# mipi_to_lvds.net
KiCad netlist of a schematic drawn in Altium Designer
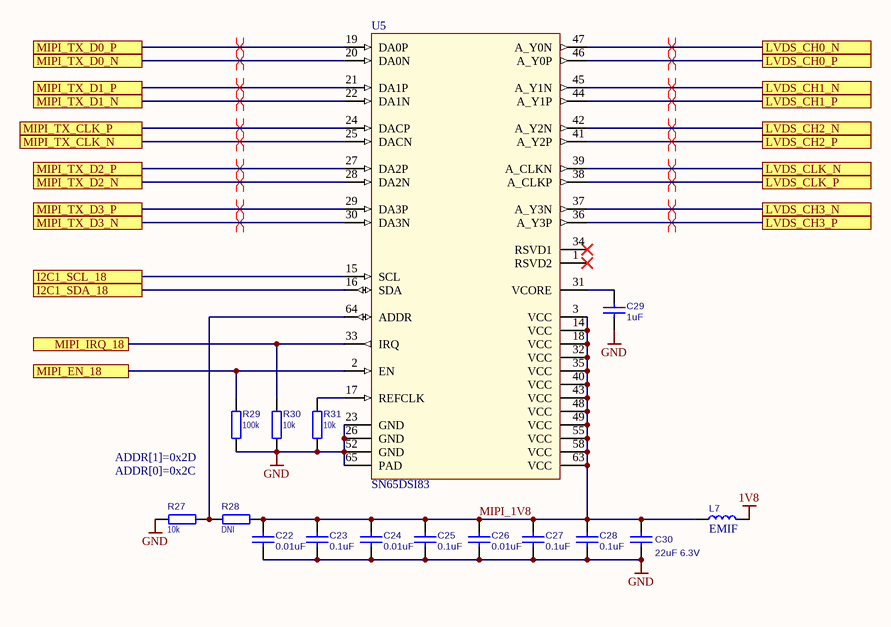
[diagram p0: mipi_to_lvds.SchDoc]

(export (version "E")
  (design (tool "Eeschema 10.0.6"))
  (components
    (comp (ref "C22")
      (value "0.01uF")
      (footprint "Capacitors:C0603")
      (description "CAP_NPOL")
      (fields (field (name "Comment") "CL10B103KB8NNNC"))
      (libsource (lib "capacitors") (part "CAP_NPOL"))
    )
    (comp (ref "C23")
      (value "0.1uF")
      (footprint "Capacitors:C0603")
      (description "CAP_NPOL")
      (fields (field (name "Comment") "C1608X7R1H104K080AA"))
      (libsource (lib "capacitors") (part "CAP_NPOL"))
    )
    (comp (ref "C24")
      (value "0.01uF")
      (footprint "Capacitors:C0603")
      (description "CAP_NPOL")
      (fields (field (name "Comment") "CL10B103KB8NNNC"))
      (libsource (lib "capacitors") (part "CAP_NPOL"))
    )
    (comp (ref "C25")
      (value "0.1uF")
      (footprint "Capacitors:C0603")
      (description "CAP_NPOL")
      (fields (field (name "Comment") "C1608X7R1H104K080AA"))
      (libsource (lib "capacitors") (part "CAP_NPOL"))
    )
    (comp (ref "C26")
      (value "0.01uF")
      (footprint "Capacitors:C0603")
      (description "CAP_NPOL")
      (fields (field (name "Comment") "CL10B103KB8NNNC"))
      (libsource (lib "capacitors") (part "CAP_NPOL"))
    )
    (comp (ref "C27")
      (value "0.1uF")
      (footprint "Capacitors:C0603")
      (description "CAP_NPOL")
      (fields (field (name "Comment") "C1608X7R1H104K080AA"))
      (libsource (lib "capacitors") (part "CAP_NPOL"))
    )
    (comp (ref "C28")
      (value "0.1uF")
      (footprint "Capacitors:C0603")
      (description "CAP_NPOL")
      (fields (field (name "Comment") "C1608X7R1H104K080AA"))
      (libsource (lib "capacitors") (part "CAP_NPOL"))
    )
    (comp (ref "C29")
      (value "1uF")
      (footprint "Capacitors:C0603")
      (description "CAP_NPOL")
      (fields (field (name "Comment") "CL21B105KAFNNNE"))
      (libsource (lib "capacitors") (part "CAP_NPOL"))
    )
    (comp (ref "C30")
      (value "22uF 6.3V")
      (footprint "Capacitors:C0805")
      (description "CAP_NPOL")
      (fields (field (name "Comment") "CL21A226MQQNNNE"))
      (libsource (lib "capacitors") (part "CAP_NPOL"))
    )
    (comp (ref "L7")
      (value "EMIF")
      (footprint "IND0805")
      (description "IND_WO_IRON")
      (fields (field (name "Comment") "BLM21PG221SN1D"))
      (libsource (lib "inductors") (part "IND_WO_IRON"))
    )
    (comp (ref "R27")
      (value "10k")
      (footprint "R0603")
      (description "RES")
      (libsource (lib "resistors") (part "RESISTOR"))
    )
    (comp (ref "R28")
      (value "DNI")
      (footprint "R0603")
      (description "RES")
      (libsource (lib "resistors") (part "RESISTOR"))
    )
    (comp (ref "R29")
      (value "100k")
      (footprint "R0603")
      (description "RES")
      (fields (field (name "Comment") "10k"))
      (libsource (lib "resistors") (part "RESISTOR"))
    )
    (comp (ref "R30")
      (value "10k")
      (footprint "R0603")
      (description "RES")
      (libsource (lib "resistors") (part "RESISTOR"))
    )
    (comp (ref "R31")
      (value "10k")
      (footprint "R0603")
      (description "RES")
      (libsource (lib "resistors") (part "RESISTOR"))
    )
    (comp (ref "U5")
      (value "SN65DSI83")
      (footprint "HPM064_N")
      (description "Single-Channel MIPI® DSI to Single-Link LVDS Bridge")
      (libsource (lib "SN65DSI83") (part "SN65DSI83"))
    )
  )
  (nets
    (net (code "1") (name "/I2C1_SCL_18") (class "Default")
      (node (ref "U5") (pin "15") (pinfunction "SCL_15") (pintype "input"))
    )
    (net (code "2") (name "/I2C1_SDA_18") (class "Default")
      (node (ref "U5") (pin "16") (pinfunction "SDA_16") (pintype "bidirectional"))
    )
    (net (code "3") (name "/LVDS_CH0_N") (class "Default")
      (node (ref "U5") (pin "47") (pinfunction "A_Y0N_47") (pintype "output"))
    )
    (net (code "4") (name "/LVDS_CH0_P") (class "Default")
      (node (ref "U5") (pin "46") (pinfunction "A_Y0P_46") (pintype "output"))
    )
    (net (code "5") (name "/LVDS_CH1_N") (class "Default")
      (node (ref "U5") (pin "45") (pinfunction "A_Y1N_45") (pintype "output"))
    )
    (net (code "6") (name "/LVDS_CH1_P") (class "Default")
      (node (ref "U5") (pin "44") (pinfunction "A_Y1P_44") (pintype "output"))
    )
    (net (code "7") (name "/LVDS_CH2_N") (class "Default")
      (node (ref "U5") (pin "42") (pinfunction "A_Y2N_42") (pintype "output"))
    )
    (net (code "8") (name "/LVDS_CH2_P") (class "Default")
      (node (ref "U5") (pin "41") (pinfunction "A_Y2P_41") (pintype "output"))
    )
    (net (code "9") (name "/LVDS_CH3_N") (class "Default")
      (node (ref "U5") (pin "37") (pinfunction "A_Y3N_37") (pintype "output"))
    )
    (net (code "10") (name "/LVDS_CH3_P") (class "Default")
      (node (ref "U5") (pin "36") (pinfunction "A_Y3P_36") (pintype "output"))
    )
    (net (code "11") (name "/LVDS_CLK_N") (class "Default")
      (node (ref "U5") (pin "39") (pinfunction "A_CLKN_39") (pintype "output"))
    )
    (net (code "12") (name "/LVDS_CLK_P") (class "Default")
      (node (ref "U5") (pin "38") (pinfunction "A_CLKP_38") (pintype "output"))
    )
    (net (code "13") (name "/MIPI_1V8") (class "Default")
      (node (ref "C22") (pin "1") (pinfunction "1_1") (pintype "passive"))
      (node (ref "C23") (pin "2") (pinfunction "2_2") (pintype "passive"))
      (node (ref "C24") (pin "1") (pinfunction "1_1") (pintype "passive"))
      (node (ref "C25") (pin "2") (pinfunction "2_2") (pintype "passive"))
      (node (ref "C26") (pin "1") (pinfunction "1_1") (pintype "passive"))
      (node (ref "C27") (pin "2") (pinfunction "2_2") (pintype "passive"))
      (node (ref "C28") (pin "2") (pinfunction "2_2") (pintype "passive"))
      (node (ref "C30") (pin "2") (pinfunction "2_2") (pintype "passive"))
      (node (ref "L7") (pin "1") (pintype "passive"))
      (node (ref "R28") (pin "2") (pinfunction "2_2") (pintype "passive"))
      (node (ref "U5") (pin "14") (pinfunction "VCC_14") (pintype "power_in"))
      (node (ref "U5") (pin "18") (pinfunction "VCC_18") (pintype "power_in"))
      (node (ref "U5") (pin "3") (pinfunction "VCC_3") (pintype "power_in"))
      (node (ref "U5") (pin "32") (pinfunction "VCC_32") (pintype "power_in"))
      (node (ref "U5") (pin "35") (pinfunction "VCC_35") (pintype "power_in"))
      (node (ref "U5") (pin "40") (pinfunction "VCC_40") (pintype "power_in"))
      (node (ref "U5") (pin "43") (pinfunction "VCC_43") (pintype "power_in"))
      (node (ref "U5") (pin "48") (pinfunction "VCC_48") (pintype "power_in"))
      (node (ref "U5") (pin "49") (pinfunction "VCC_49") (pintype "power_in"))
      (node (ref "U5") (pin "55") (pinfunction "VCC_55") (pintype "power_in"))
      (node (ref "U5") (pin "58") (pinfunction "VCC_58") (pintype "power_in"))
      (node (ref "U5") (pin "63") (pinfunction "VCC_63") (pintype "power_in"))
    )
    (net (code "14") (name "/MIPI_EN_18") (class "Default")
      (node (ref "R29") (pin "2") (pinfunction "2_2") (pintype "passive"))
      (node (ref "U5") (pin "2") (pinfunction "EN_2") (pintype "input"))
    )
    (net (code "15") (name "/MIPI_IRQ_18") (class "Default")
      (node (ref "R30") (pin "2") (pinfunction "2_2") (pintype "passive"))
      (node (ref "U5") (pin "33") (pinfunction "IRQ_33") (pintype "output"))
    )
    (net (code "16") (name "/MIPI_TX_CLK_N") (class "Default")
      (node (ref "U5") (pin "25") (pinfunction "DACN_25") (pintype "input"))
    )
    (net (code "17") (name "/MIPI_TX_CLK_P") (class "Default")
      (node (ref "U5") (pin "24") (pinfunction "DACP_24") (pintype "input"))
    )
    (net (code "18") (name "/MIPI_TX_D0_N") (class "Default")
      (node (ref "U5") (pin "20") (pinfunction "DA0N_20") (pintype "input"))
    )
    (net (code "19") (name "/MIPI_TX_D0_P") (class "Default")
      (node (ref "U5") (pin "19") (pinfunction "DA0P_19") (pintype "input"))
    )
    (net (code "20") (name "/MIPI_TX_D1_N") (class "Default")
      (node (ref "U5") (pin "22") (pinfunction "DA1N_22") (pintype "input"))
    )
    (net (code "21") (name "/MIPI_TX_D1_P") (class "Default")
      (node (ref "U5") (pin "21") (pinfunction "DA1P_21") (pintype "input"))
    )
    (net (code "22") (name "/MIPI_TX_D2_N") (class "Default")
      (node (ref "U5") (pin "28") (pinfunction "DA2N_28") (pintype "input"))
    )
    (net (code "23") (name "/MIPI_TX_D2_P") (class "Default")
      (node (ref "U5") (pin "27") (pinfunction "DA2P_27") (pintype "input"))
    )
    (net (code "24") (name "/MIPI_TX_D3_N") (class "Default")
      (node (ref "U5") (pin "30") (pinfunction "DA3N_30") (pintype "input"))
    )
    (net (code "25") (name "/MIPI_TX_D3_P") (class "Default")
      (node (ref "U5") (pin "29") (pinfunction "DA3P_29") (pintype "input"))
    )
    (net (code "26") (name "1V8") (class "Default") (node (ref "L7") (pin "2") (pintype "passive")))
    (net (code "27") (name "GND") (class "Default")
      (node (ref "C22") (pin "2") (pinfunction "2_2") (pintype "passive"))
      (node (ref "C23") (pin "1") (pinfunction "1_1") (pintype "passive"))
      (node (ref "C24") (pin "2") (pinfunction "2_2") (pintype "passive"))
      (node (ref "C25") (pin "1") (pinfunction "1_1") (pintype "passive"))
      (node (ref "C26") (pin "2") (pinfunction "2_2") (pintype "passive"))
      (node (ref "C27") (pin "1") (pinfunction "1_1") (pintype "passive"))
      (node (ref "C28") (pin "1") (pinfunction "1_1") (pintype "passive"))
      (node (ref "C29") (pin "1") (pinfunction "1_1") (pintype "passive"))
      (node (ref "C30") (pin "1") (pinfunction "1_1") (pintype "passive"))
      (node (ref "R27") (pin "1") (pinfunction "1_1") (pintype "passive"))
      (node (ref "R29") (pin "1") (pinfunction "1_1") (pintype "passive"))
      (node (ref "R30") (pin "1") (pinfunction "1_1") (pintype "passive"))
      (node (ref "R31") (pin "1") (pinfunction "1_1") (pintype "passive"))
      (node (ref "U5") (pin "23") (pinfunction "GND_23") (pintype "power_in"))
      (node (ref "U5") (pin "26") (pinfunction "GND_26") (pintype "power_in"))
      (node (ref "U5") (pin "52") (pinfunction "GND_52") (pintype "power_in"))
      (node (ref "U5") (pin "65") (pinfunction "PAD_65") (pintype "power_in"))
    )
    (net (code "28") (name "Net-(U5-ADDR)") (class "Default")
      (node (ref "R27") (pin "2") (pinfunction "2_2") (pintype "passive"))
      (node (ref "R28") (pin "1") (pinfunction "1_1") (pintype "passive"))
      (node (ref "U5") (pin "64") (pinfunction "ADDR_64") (pintype "bidirectional"))
    )
    (net (code "29") (name "Net-(U5-REFCLK)") (class "Default")
      (node (ref "R31") (pin "2") (pinfunction "2_2") (pintype "passive"))
      (node (ref "U5") (pin "17") (pinfunction "REFCLK_17") (pintype "input"))
    )
    (net (code "30") (name "Net-(U5-VCORE)") (class "Default")
      (node (ref "C29") (pin "2") (pinfunction "2_2") (pintype "passive"))
      (node (ref "U5") (pin "31") (pinfunction "VCORE_31") (pintype "power_in"))
    )
    (net (code "31") (name "unconnected-(U5-RSVD1-Pad34)") (class "Default")
      (node (ref "U5") (pin "34") (pinfunction "RSVD1_34") (pintype "passive+no_connect"))
    )
    (net (code "32") (name "unconnected-(U5-RSVD2-Pad1)") (class "Default")
      (node (ref "U5") (pin "1") (pinfunction "RSVD2_1") (pintype "passive+no_connect"))
    )
  )
)
